# ADG714.net
KiCad netlist of a schematic drawn in Altium Designer
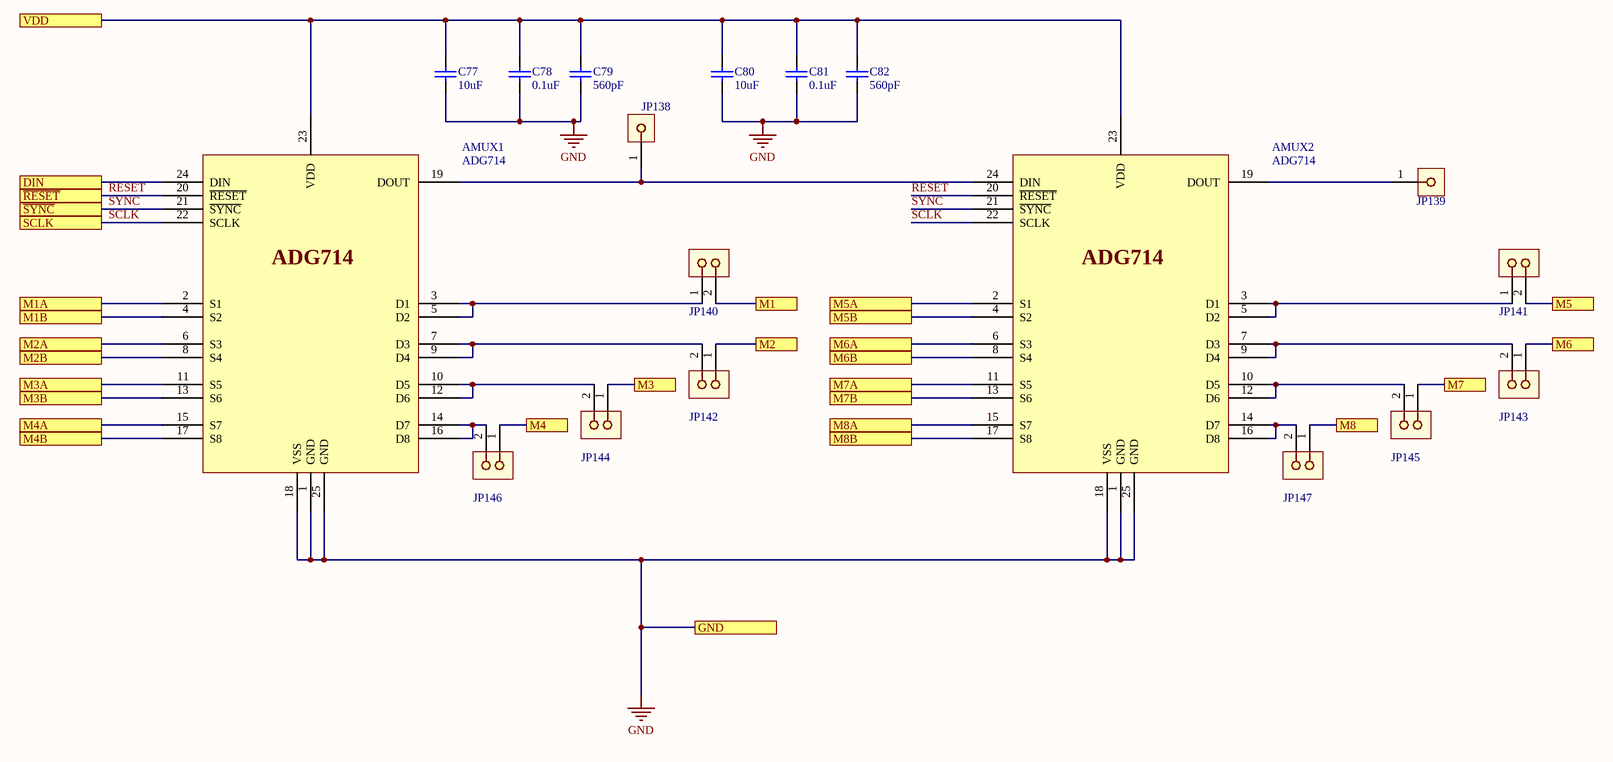
[diagram p0: ADG714.SchDoc]

(export (version "E")
  (design (tool "Eeschema 10.0.6"))
  (components
    (comp (ref "AMUX1")
      (value "ADG714")
      (footprint "ADG714BCPZ")
      (description "Analog MUX")
      (libsource (lib "Chip1_TestBoard") (part "ADG714"))
    )
    (comp (ref "AMUX2")
      (value "ADG714")
      (footprint "ADG714BCPZ")
      (description "Analog MUX")
      (libsource (lib "Chip1_TestBoard") (part "ADG714"))
    )
    (comp (ref "C77")
      (value "10uF")
      (footprint "CLS_Library:C0805")
      (description "Cap 10uF")
      (fields
        (field (name "MANUFACTURER") "Taiyo Yuden")
        (field (name "MANUFACTURER PART NUMBER") "UMK212SD103KD-T")
      )
      (libsource (lib "Chip1_TestBoard") (part "Cap 10uF"))
    )
    (comp (ref "C78")
      (value "0.1uF")
      (footprint "CLS_Library:C0805")
      (description "Cap 0.1uF")
      (fields
        (field (name "MANUFACTURER") "Taiyo Yuden")
        (field (name "MANUFACTURER PART NUMBER") "UMK212SD103KD-T")
      )
      (libsource (lib "Chip1_TestBoard") (part "Cap 0.1uF"))
    )
    (comp (ref "C79")
      (value "560pF")
      (footprint "CLS_Library:C0805")
      (description "Cap 560pF")
      (fields
        (field (name "MANUFACTURER") "Taiyo Yuden")
        (field (name "MANUFACTURER PART NUMBER") "UMK212SD103KD-T")
      )
      (libsource (lib "Chip1_TestBoard") (part "Cap 560pF"))
    )
    (comp (ref "C80")
      (value "10uF")
      (footprint "CLS_Library:C0805")
      (description "Cap 10uF")
      (fields
        (field (name "MANUFACTURER") "Taiyo Yuden")
        (field (name "MANUFACTURER PART NUMBER") "UMK212SD103KD-T")
      )
      (libsource (lib "Chip1_TestBoard") (part "Cap 10uF"))
    )
    (comp (ref "C81")
      (value "0.1uF")
      (footprint "CLS_Library:C0805")
      (description "Cap 0.1uF")
      (fields
        (field (name "MANUFACTURER") "Taiyo Yuden")
        (field (name "MANUFACTURER PART NUMBER") "UMK212SD103KD-T")
      )
      (libsource (lib "Chip1_TestBoard") (part "Cap 0.1uF"))
    )
    (comp (ref "C82")
      (value "560pF")
      (footprint "CLS_Library:C0805")
      (description "Cap 560pF")
      (fields
        (field (name "MANUFACTURER") "Taiyo Yuden")
        (field (name "MANUFACTURER PART NUMBER") "UMK212SD103KD-T")
      )
      (libsource (lib "Chip1_TestBoard") (part "Cap 560pF"))
    )
    (comp (ref "JP138")
      (value "01x01")
      (footprint "01x01_0_0.1in_th_straight_b_nom")
      (description "01X01 generic terminal connector")
      (libsource (lib "Chip1_TestBoard") (part "01x01"))
    )
    (comp (ref "JP139")
      (value "01x01")
      (footprint "01x01_0_0.1in_th_straight_b_nom")
      (description "01X01 generic terminal connector")
      (libsource (lib "") (part "01x01_1"))
    )
    (comp (ref "JP140")
      (value "01x02")
      (footprint "01x02_0.1in_th_straight_b_nom")
      (description "01X02 generic terminal connector")
      (libsource (lib "") (part "01x02_1"))
    )
    (comp (ref "JP141")
      (value "01x02")
      (footprint "01x02_0.1in_th_straight_b_nom")
      (description "01X02 generic terminal connector")
      (libsource (lib "") (part "01x02_1"))
    )
    (comp (ref "JP142")
      (value "01x02")
      (footprint "01x02_0.1in_th_straight_b_nom")
      (description "01X02 generic terminal connector")
      (libsource (lib "Chip1_TestBoard") (part "01x02"))
    )
    (comp (ref "JP143")
      (value "01x02")
      (footprint "01x02_0.1in_th_straight_b_nom")
      (description "01X02 generic terminal connector")
      (libsource (lib "Chip1_TestBoard") (part "01x02"))
    )
    (comp (ref "JP144")
      (value "01x02")
      (footprint "01x02_0.1in_th_straight_b_nom")
      (description "01X02 generic terminal connector")
      (libsource (lib "Chip1_TestBoard") (part "01x02"))
    )
    (comp (ref "JP145")
      (value "01x02")
      (footprint "01x02_0.1in_th_straight_b_nom")
      (description "01X02 generic terminal connector")
      (libsource (lib "Chip1_TestBoard") (part "01x02"))
    )
    (comp (ref "JP146")
      (value "01x02")
      (footprint "01x02_0.1in_th_straight_b_nom")
      (description "01X02 generic terminal connector")
      (libsource (lib "Chip1_TestBoard") (part "01x02"))
    )
    (comp (ref "JP147")
      (value "01x02")
      (footprint "01x02_0.1in_th_straight_b_nom")
      (description "01X02 generic terminal connector")
      (libsource (lib "Chip1_TestBoard") (part "01x02"))
    )
  )
  (nets
    (net (code "1") (name "/DIN") (class "Default")
      (node (ref "AMUX1") (pin "24") (pinfunction "DIN_24") (pintype "passive"))
    )
    (net (code "2") (name "/M1") (class "Default")
      (node (ref "JP140") (pin "2") (pinfunction "2_2") (pintype "passive"))
    )
    (net (code "3") (name "/M1A") (class "Default")
      (node (ref "AMUX1") (pin "2") (pinfunction "S1_2") (pintype "passive"))
    )
    (net (code "4") (name "/M1B") (class "Default")
      (node (ref "AMUX1") (pin "4") (pinfunction "S2_4") (pintype "passive"))
    )
    (net (code "5") (name "/M2") (class "Default")
      (node (ref "JP142") (pin "1") (pinfunction "1_1") (pintype "passive"))
    )
    (net (code "6") (name "/M2A") (class "Default")
      (node (ref "AMUX1") (pin "6") (pinfunction "S3_6") (pintype "passive"))
    )
    (net (code "7") (name "/M2B") (class "Default")
      (node (ref "AMUX1") (pin "8") (pinfunction "S4_8") (pintype "passive"))
    )
    (net (code "8") (name "/M3") (class "Default")
      (node (ref "JP144") (pin "1") (pinfunction "1_1") (pintype "passive"))
    )
    (net (code "9") (name "/M3A") (class "Default")
      (node (ref "AMUX1") (pin "11") (pinfunction "S5_11") (pintype "passive"))
    )
    (net (code "10") (name "/M3B") (class "Default")
      (node (ref "AMUX1") (pin "13") (pinfunction "S6_13") (pintype "passive"))
    )
    (net (code "11") (name "/M4") (class "Default")
      (node (ref "JP146") (pin "1") (pinfunction "1_1") (pintype "passive"))
    )
    (net (code "12") (name "/M4A") (class "Default")
      (node (ref "AMUX1") (pin "15") (pinfunction "S7_15") (pintype "passive"))
    )
    (net (code "13") (name "/M4B") (class "Default")
      (node (ref "AMUX1") (pin "17") (pinfunction "S8_17") (pintype "passive"))
    )
    (net (code "14") (name "/M5") (class "Default")
      (node (ref "JP141") (pin "2") (pinfunction "2_2") (pintype "passive"))
    )
    (net (code "15") (name "/M5A") (class "Default")
      (node (ref "AMUX2") (pin "2") (pinfunction "S1_2") (pintype "passive"))
    )
    (net (code "16") (name "/M5B") (class "Default")
      (node (ref "AMUX2") (pin "4") (pinfunction "S2_4") (pintype "passive"))
    )
    (net (code "17") (name "/M6") (class "Default")
      (node (ref "JP143") (pin "1") (pinfunction "1_1") (pintype "passive"))
    )
    (net (code "18") (name "/M6A") (class "Default")
      (node (ref "AMUX2") (pin "6") (pinfunction "S3_6") (pintype "passive"))
    )
    (net (code "19") (name "/M6B") (class "Default")
      (node (ref "AMUX2") (pin "8") (pinfunction "S4_8") (pintype "passive"))
    )
    (net (code "20") (name "/M7") (class "Default")
      (node (ref "JP145") (pin "1") (pinfunction "1_1") (pintype "passive"))
    )
    (net (code "21") (name "/M7A") (class "Default")
      (node (ref "AMUX2") (pin "11") (pinfunction "S5_11") (pintype "passive"))
    )
    (net (code "22") (name "/M7B") (class "Default")
      (node (ref "AMUX2") (pin "13") (pinfunction "S6_13") (pintype "passive"))
    )
    (net (code "23") (name "/M8") (class "Default")
      (node (ref "JP147") (pin "1") (pinfunction "1_1") (pintype "passive"))
    )
    (net (code "24") (name "/M8A") (class "Default")
      (node (ref "AMUX2") (pin "15") (pinfunction "S7_15") (pintype "passive"))
    )
    (net (code "25") (name "/M8B") (class "Default")
      (node (ref "AMUX2") (pin "17") (pinfunction "S8_17") (pintype "passive"))
    )
    (net (code "26") (name "/SCLK") (class "Default")
      (node (ref "AMUX1") (pin "22") (pinfunction "SCLK_22") (pintype "passive"))
      (node (ref "AMUX2") (pin "22") (pinfunction "SCLK_22") (pintype "passive"))
    )
    (net (code "27") (name "/VDD") (class "Default")
      (node (ref "AMUX1") (pin "23") (pinfunction "VDD_23") (pintype "passive"))
      (node (ref "AMUX2") (pin "23") (pinfunction "VDD_23") (pintype "passive"))
      (node (ref "C77") (pin "2") (pinfunction "2_2") (pintype "passive"))
      (node (ref "C78") (pin "2") (pinfunction "2_2") (pintype "passive"))
      (node (ref "C79") (pin "2") (pinfunction "2_2") (pintype "passive"))
      (node (ref "C80") (pin "2") (pinfunction "2_2") (pintype "passive"))
      (node (ref "C81") (pin "2") (pinfunction "2_2") (pintype "passive"))
      (node (ref "C82") (pin "2") (pinfunction "2_2") (pintype "passive"))
    )
    (net (code "28") (name "/~{RESET}") (class "Default")
      (node (ref "AMUX1") (pin "20") (pinfunction "~{RESET}_20") (pintype "passive"))
      (node (ref "AMUX2") (pin "20") (pinfunction "~{RESET}_20") (pintype "passive"))
    )
    (net (code "29") (name "/~{SYNC}") (class "Default")
      (node (ref "AMUX1") (pin "21") (pinfunction "~{SYNC}_21") (pintype "passive"))
      (node (ref "AMUX2") (pin "21") (pinfunction "~{SYNC}_21") (pintype "passive"))
    )
    (net (code "30") (name "GND") (class "Default")
      (node (ref "AMUX1") (pin "1") (pinfunction "GND_1") (pintype "passive"))
      (node (ref "AMUX1") (pin "18") (pinfunction "VSS_18") (pintype "passive"))
      (node (ref "AMUX1") (pin "25") (pinfunction "GND_25") (pintype "passive"))
      (node (ref "AMUX2") (pin "1") (pinfunction "GND_1") (pintype "passive"))
      (node (ref "AMUX2") (pin "18") (pinfunction "VSS_18") (pintype "passive"))
      (node (ref "AMUX2") (pin "25") (pinfunction "GND_25") (pintype "passive"))
      (node (ref "C77") (pin "1") (pinfunction "1_1") (pintype "passive"))
      (node (ref "C78") (pin "1") (pinfunction "1_1") (pintype "passive"))
      (node (ref "C79") (pin "1") (pinfunction "1_1") (pintype "passive"))
      (node (ref "C80") (pin "1") (pinfunction "1_1") (pintype "passive"))
      (node (ref "C81") (pin "1") (pinfunction "1_1") (pintype "passive"))
      (node (ref "C82") (pin "1") (pinfunction "1_1") (pintype "passive"))
    )
    (net (code "31") (name "Net-(AMUX1-D1)") (class "Default")
      (node (ref "AMUX1") (pin "3") (pinfunction "D1_3") (pintype "passive"))
      (node (ref "AMUX1") (pin "5") (pinfunction "D2_5") (pintype "passive"))
      (node (ref "JP140") (pin "1") (pinfunction "1_1") (pintype "passive"))
    )
    (net (code "32") (name "Net-(AMUX1-D3)") (class "Default")
      (node (ref "AMUX1") (pin "7") (pinfunction "D3_7") (pintype "passive"))
      (node (ref "AMUX1") (pin "9") (pinfunction "D4_9") (pintype "passive"))
      (node (ref "JP142") (pin "2") (pinfunction "2_2") (pintype "passive"))
    )
    (net (code "33") (name "Net-(AMUX1-D5)") (class "Default")
      (node (ref "AMUX1") (pin "10") (pinfunction "D5_10") (pintype "passive"))
      (node (ref "AMUX1") (pin "12") (pinfunction "D6_12") (pintype "passive"))
      (node (ref "JP144") (pin "2") (pinfunction "2_2") (pintype "passive"))
    )
    (net (code "34") (name "Net-(AMUX1-D7)") (class "Default")
      (node (ref "AMUX1") (pin "14") (pinfunction "D7_14") (pintype "passive"))
      (node (ref "AMUX1") (pin "16") (pinfunction "D8_16") (pintype "passive"))
      (node (ref "JP146") (pin "2") (pinfunction "2_2") (pintype "passive"))
    )
    (net (code "35") (name "Net-(AMUX1-DOUT)") (class "Default")
      (node (ref "AMUX1") (pin "19") (pinfunction "DOUT_19") (pintype "passive"))
      (node (ref "AMUX2") (pin "24") (pinfunction "DIN_24") (pintype "passive"))
      (node (ref "JP138") (pin "1") (pinfunction "1_1") (pintype "passive"))
    )
    (net (code "36") (name "Net-(AMUX2-D1)") (class "Default")
      (node (ref "AMUX2") (pin "3") (pinfunction "D1_3") (pintype "passive"))
      (node (ref "AMUX2") (pin "5") (pinfunction "D2_5") (pintype "passive"))
      (node (ref "JP141") (pin "1") (pinfunction "1_1") (pintype "passive"))
    )
    (net (code "37") (name "Net-(AMUX2-D3)") (class "Default")
      (node (ref "AMUX2") (pin "7") (pinfunction "D3_7") (pintype "passive"))
      (node (ref "AMUX2") (pin "9") (pinfunction "D4_9") (pintype "passive"))
      (node (ref "JP143") (pin "2") (pinfunction "2_2") (pintype "passive"))
    )
    (net (code "38") (name "Net-(AMUX2-D5)") (class "Default")
      (node (ref "AMUX2") (pin "10") (pinfunction "D5_10") (pintype "passive"))
      (node (ref "AMUX2") (pin "12") (pinfunction "D6_12") (pintype "passive"))
      (node (ref "JP145") (pin "2") (pinfunction "2_2") (pintype "passive"))
    )
    (net (code "39") (name "Net-(AMUX2-D7)") (class "Default")
      (node (ref "AMUX2") (pin "14") (pinfunction "D7_14") (pintype "passive"))
      (node (ref "AMUX2") (pin "16") (pinfunction "D8_16") (pintype "passive"))
      (node (ref "JP147") (pin "2") (pinfunction "2_2") (pintype "passive"))
    )
    (net (code "40") (name "Net-(AMUX2-DOUT)") (class "Default")
      (node (ref "AMUX2") (pin "19") (pinfunction "DOUT_19") (pintype "passive"))
      (node (ref "JP139") (pin "1") (pinfunction "1_1") (pintype "passive"))
    )
  )
)
